# Amp_Kit_v6_3_4.net
KiCad netlist of a schematic drawn in EAGLE
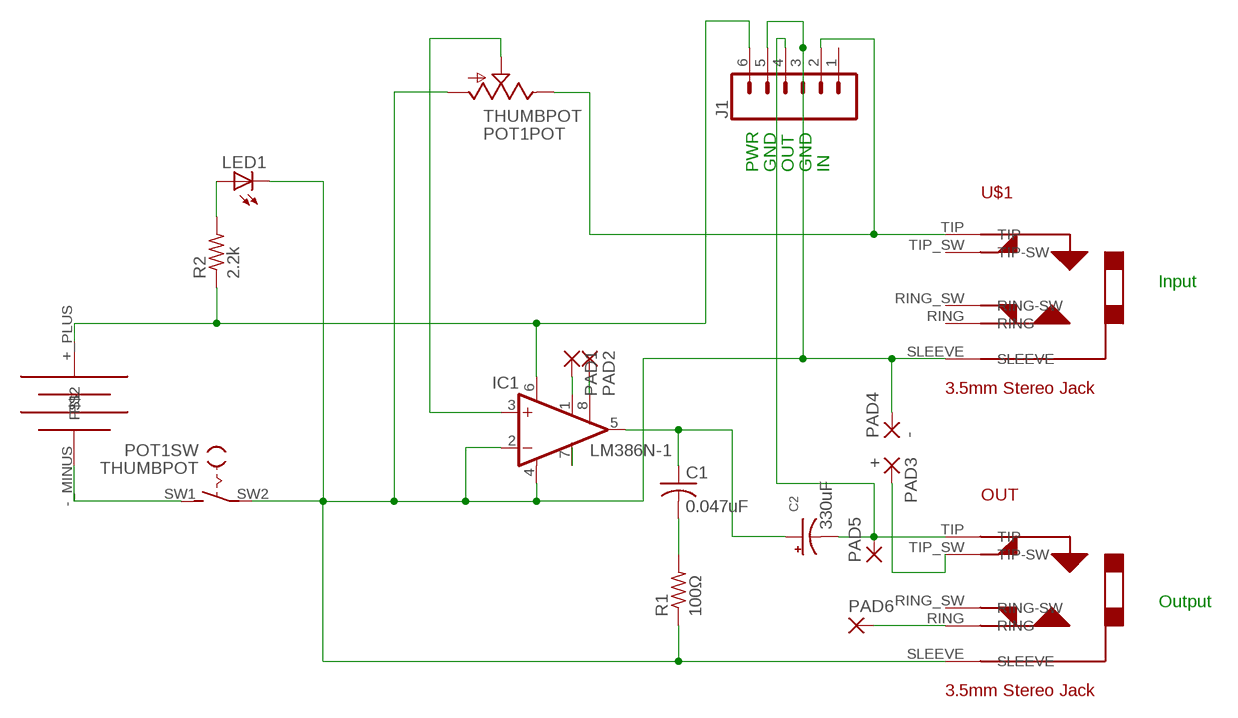
[diagram p0: schematic, sheet 1]

(export (version "E")
  (design (tool "Eeschema 10.0.6"))
  (components
    (comp (ref "C1")
      (value "0.047uF")
      (footprint "eagle-import:C050-024X044")
      (libsource (lib "eagle-import") (part "C-US050-024X044"))
    )
    (comp (ref "C2")
      (value "330uF")
      (footprint "eagle-import:E1,8-4")
      (libsource (lib "eagle-import") (part "CPOL-USE1.8-4"))
    )
    (comp (ref "IC1")
      (value "LM386N-1")
      (footprint "eagle-import:DIL08")
      (libsource (lib "eagle-import") (part "LM386?-N1"))
    )
    (comp (ref "J1")
      (value "CONN_06NO_SILK_FEMALE_PTH")
      (footprint "eagle-import:1X06_NO_SILK")
      (libsource (lib "eagle-import") (part "CONN_06NO_SILK_FEMALE_PTH"))
    )
    (comp (ref "LED1")
      (value "LED5MM")
      (footprint "eagle-import:LED5MM")
      (libsource (lib "eagle-import") (part "LED5MM"))
    )
    (comp (ref "OUT")
      (value "CUI_STEREO_JACK")
      (footprint "eagle-import:CUI_STEREO_JACK")
      (libsource (lib "eagle-import") (part "CUI_STEREO_JACK"))
    )
    (comp (ref "PAD1")
      (value "SMD2")
      (footprint "eagle-import:SMD1,27-2,54")
      (libsource (lib "eagle-import") (part "SMD2"))
    )
    (comp (ref "PAD2")
      (value "SMD2")
      (footprint "eagle-import:SMD1,27-2,54")
      (libsource (lib "eagle-import") (part "SMD2"))
    )
    (comp (ref "PAD3")
      (value "+")
      (footprint "eagle-import:4,16O1,6")
      (libsource (lib "eagle-import") (part "WIREPAD4,16O1,6"))
    )
    (comp (ref "PAD4")
      (value "-")
      (footprint "eagle-import:4,16O1,6")
      (libsource (lib "eagle-import") (part "WIREPAD4,16O1,6"))
    )
    (comp (ref "PAD5")
      (value "SMD2")
      (footprint "eagle-import:SMD1,27-2,54")
      (libsource (lib "eagle-import") (part "SMD2"))
    )
    (comp (ref "PAD6")
      (value "SMD2")
      (footprint "eagle-import:SMD1,27-2,54")
      (libsource (lib "eagle-import") (part "SMD2"))
    )
    (comp (ref "POT1")
      (value "THUMBPOT")
      (footprint "eagle-import:THUMBWHEEL")
      (libsource (lib "eagle-import") (part "THUMBPOT"))
    )
    (comp (ref "R1")
      (value "100Ω")
      (footprint "eagle-import:0207_7")
      (libsource (lib "eagle-import") (part "R-US_0207/7"))
    )
    (comp (ref "R2")
      (value "2.2k")
      (footprint "eagle-import:0207_7")
      (libsource (lib "eagle-import") (part "R-US_0207/7"))
    )
    (comp (ref "U$1")
      (value "CUI_STEREO_JACK")
      (footprint "eagle-import:CUI_STEREO_JACK")
      (libsource (lib "eagle-import") (part "CUI_STEREO_JACK"))
    )
    (comp (ref "U$2")
      (value "9V_BATCLIP_AMP2")
      (footprint "eagle-import:9V_BATCLIP_AMP2")
      (libsource (lib "eagle-import") (part "9V_BATCLIP_AMP2"))
    )
  )
  (nets
    (net (code "1") (name "Net-(C1-Pad2)") (class "Default")
      (node (ref "C1") (pin "2") (pinfunction "2_2") (pintype "passive"))
      (node (ref "R1") (pin "2") (pinfunction "2_2") (pintype "passive"))
    )
    (net (code "2") (name "Net-(IC1-+IN)") (class "Default")
      (node (ref "IC1") (pin "3") (pinfunction "+IN_3") (pintype "input"))
      (node (ref "POT1") (pin "2") (pinfunction "S_2") (pintype "passive"))
    )
    (net (code "3") (name "Net-(IC1--IN)") (class "Default")
      (node (ref "IC1") (pin "2") (pinfunction "-IN_2") (pintype "input"))
      (node (ref "IC1") (pin "4") (pinfunction "GND_4") (pintype "power_in"))
      (node (ref "J1") (pin "3") (pinfunction "3_3") (pintype "passive"))
      (node (ref "J1") (pin "5") (pinfunction "5_5") (pintype "passive"))
      (node (ref "LED1") (pin "K") (pinfunction "C_K") (pintype "passive"))
      (node (ref "OUT") (pin "SLEEVE") (pinfunction "SLEEVE_SLEEVE") (pintype "bidirectional"))
      (node (ref "PAD4") (pin "1") (pinfunction "P_1") (pintype "passive"))
      (node (ref "POT1") (pin "1") (pinfunction "A_1") (pintype "passive"))
      (node (ref "POT1") (pin "SW2") (pinfunction "P_SW2") (pintype "passive"))
      (node (ref "R1") (pin "1") (pinfunction "1_1") (pintype "passive"))
      (node (ref "U$1") (pin "SLEEVE") (pinfunction "SLEEVE_SLEEVE") (pintype "bidirectional"))
    )
    (net (code "4") (name "Net-(IC1-OUT)") (class "Default")
      (node (ref "C1") (pin "1") (pinfunction "1_1") (pintype "passive"))
      (node (ref "C2") (pin "+") (pinfunction "+_+") (pintype "passive"))
      (node (ref "IC1") (pin "5") (pinfunction "OUT_5") (pintype "output"))
    )
    (net (code "5") (name "Net-(IC1-VS)") (class "Default")
      (node (ref "IC1") (pin "6") (pinfunction "VS_6") (pintype "power_in"))
      (node (ref "J1") (pin "6") (pinfunction "6_6") (pintype "passive"))
      (node (ref "R2") (pin "1") (pinfunction "1_1") (pintype "passive"))
      (node (ref "U$2") (pin "+_PLUS") (pinfunction "P$1_+_PLUS") (pintype "bidirectional"))
    )
    (net (code "6") (name "Net-(LED1-PadA)") (class "Default")
      (node (ref "LED1") (pin "A") (pinfunction "A_A") (pintype "passive"))
      (node (ref "R2") (pin "2") (pinfunction "2_2") (pintype "passive"))
    )
    (net (code "7") (name "Net-(OUT-TIP-SW)") (class "Default")
      (node (ref "OUT") (pin "TIP_SW") (pinfunction "TIP-SW_TIP_SW") (pintype "bidirectional"))
      (node (ref "PAD3") (pin "1") (pinfunction "P_1") (pintype "passive"))
    )
    (net (code "8") (name "Net-(PAD1-P)") (class "Default")
      (node (ref "IC1") (pin "1") (pinfunction "GAIN_1") (pintype "passive"))
      (node (ref "PAD1") (pin "1") (pinfunction "P_1") (pintype "passive"))
    )
    (net (code "9") (name "Net-(PAD2-P)") (class "Default")
      (node (ref "IC1") (pin "8") (pinfunction "GAIN_8") (pintype "passive"))
      (node (ref "PAD2") (pin "1") (pinfunction "P_1") (pintype "passive"))
    )
    (net (code "10") (name "Net-(PAD5-P)") (class "Default")
      (node (ref "C2") (pin "-") (pinfunction "-_-") (pintype "passive"))
      (node (ref "J1") (pin "4") (pinfunction "4_4") (pintype "passive"))
      (node (ref "OUT") (pin "TIP") (pinfunction "TIP_TIP") (pintype "bidirectional"))
      (node (ref "PAD5") (pin "1") (pinfunction "P_1") (pintype "passive"))
    )
    (net (code "11") (name "Net-(PAD6-P)") (class "Default")
      (node (ref "OUT") (pin "RING") (pinfunction "RING_RING") (pintype "bidirectional"))
      (node (ref "PAD6") (pin "1") (pinfunction "P_1") (pintype "passive"))
    )
    (net (code "12") (name "Net-(POT1A-E)") (class "Default")
      (node (ref "J1") (pin "2") (pinfunction "2_2") (pintype "passive"))
      (node (ref "POT1") (pin "3") (pinfunction "E_3") (pintype "passive"))
      (node (ref "U$1") (pin "TIP") (pinfunction "TIP_TIP") (pintype "bidirectional"))
    )
    (net (code "13") (name "Net-(POT1B-S)") (class "Default")
      (node (ref "POT1") (pin "SW1") (pinfunction "S_SW1") (pintype "passive"))
      (node (ref "U$2") (pin "-_MINUS") (pinfunction "P$2_-_MINUS") (pintype "bidirectional"))
    )
    (net (code "14") (name "unconnected-(IC1-BYPASS-Pad7)") (class "Default")
      (node (ref "IC1") (pin "7") (pinfunction "BYPASS_7") (pintype "passive"))
    )
    (net (code "15") (name "unconnected-(J1-Pad1)") (class "Default")
      (node (ref "J1") (pin "1") (pinfunction "1_1") (pintype "passive"))
    )
    (net (code "16") (name "unconnected-(OUT-RING-SW-PadRING_SW)") (class "Default")
      (node (ref "OUT") (pin "RING_SW") (pinfunction "RING-SW_RING_SW") (pintype "bidirectional"))
    )
    (net (code "17") (name "unconnected-(U$1-PadRING)") (class "Default")
      (node (ref "U$1") (pin "RING") (pinfunction "RING_RING") (pintype "bidirectional"))
    )
    (net (code "18") (name "unconnected-(U$1-RING-SW-PadRING_SW)") (class "Default")
      (node (ref "U$1") (pin "RING_SW") (pinfunction "RING-SW_RING_SW") (pintype "bidirectional"))
    )
    (net (code "19") (name "unconnected-(U$1-TIP-SW-PadTIP_SW)") (class "Default")
      (node (ref "U$1") (pin "TIP_SW") (pinfunction "TIP-SW_TIP_SW") (pintype "bidirectional"))
    )
  )
)
